# ESP32C3.net
KiCad netlist of a schematic drawn in Altium Designer
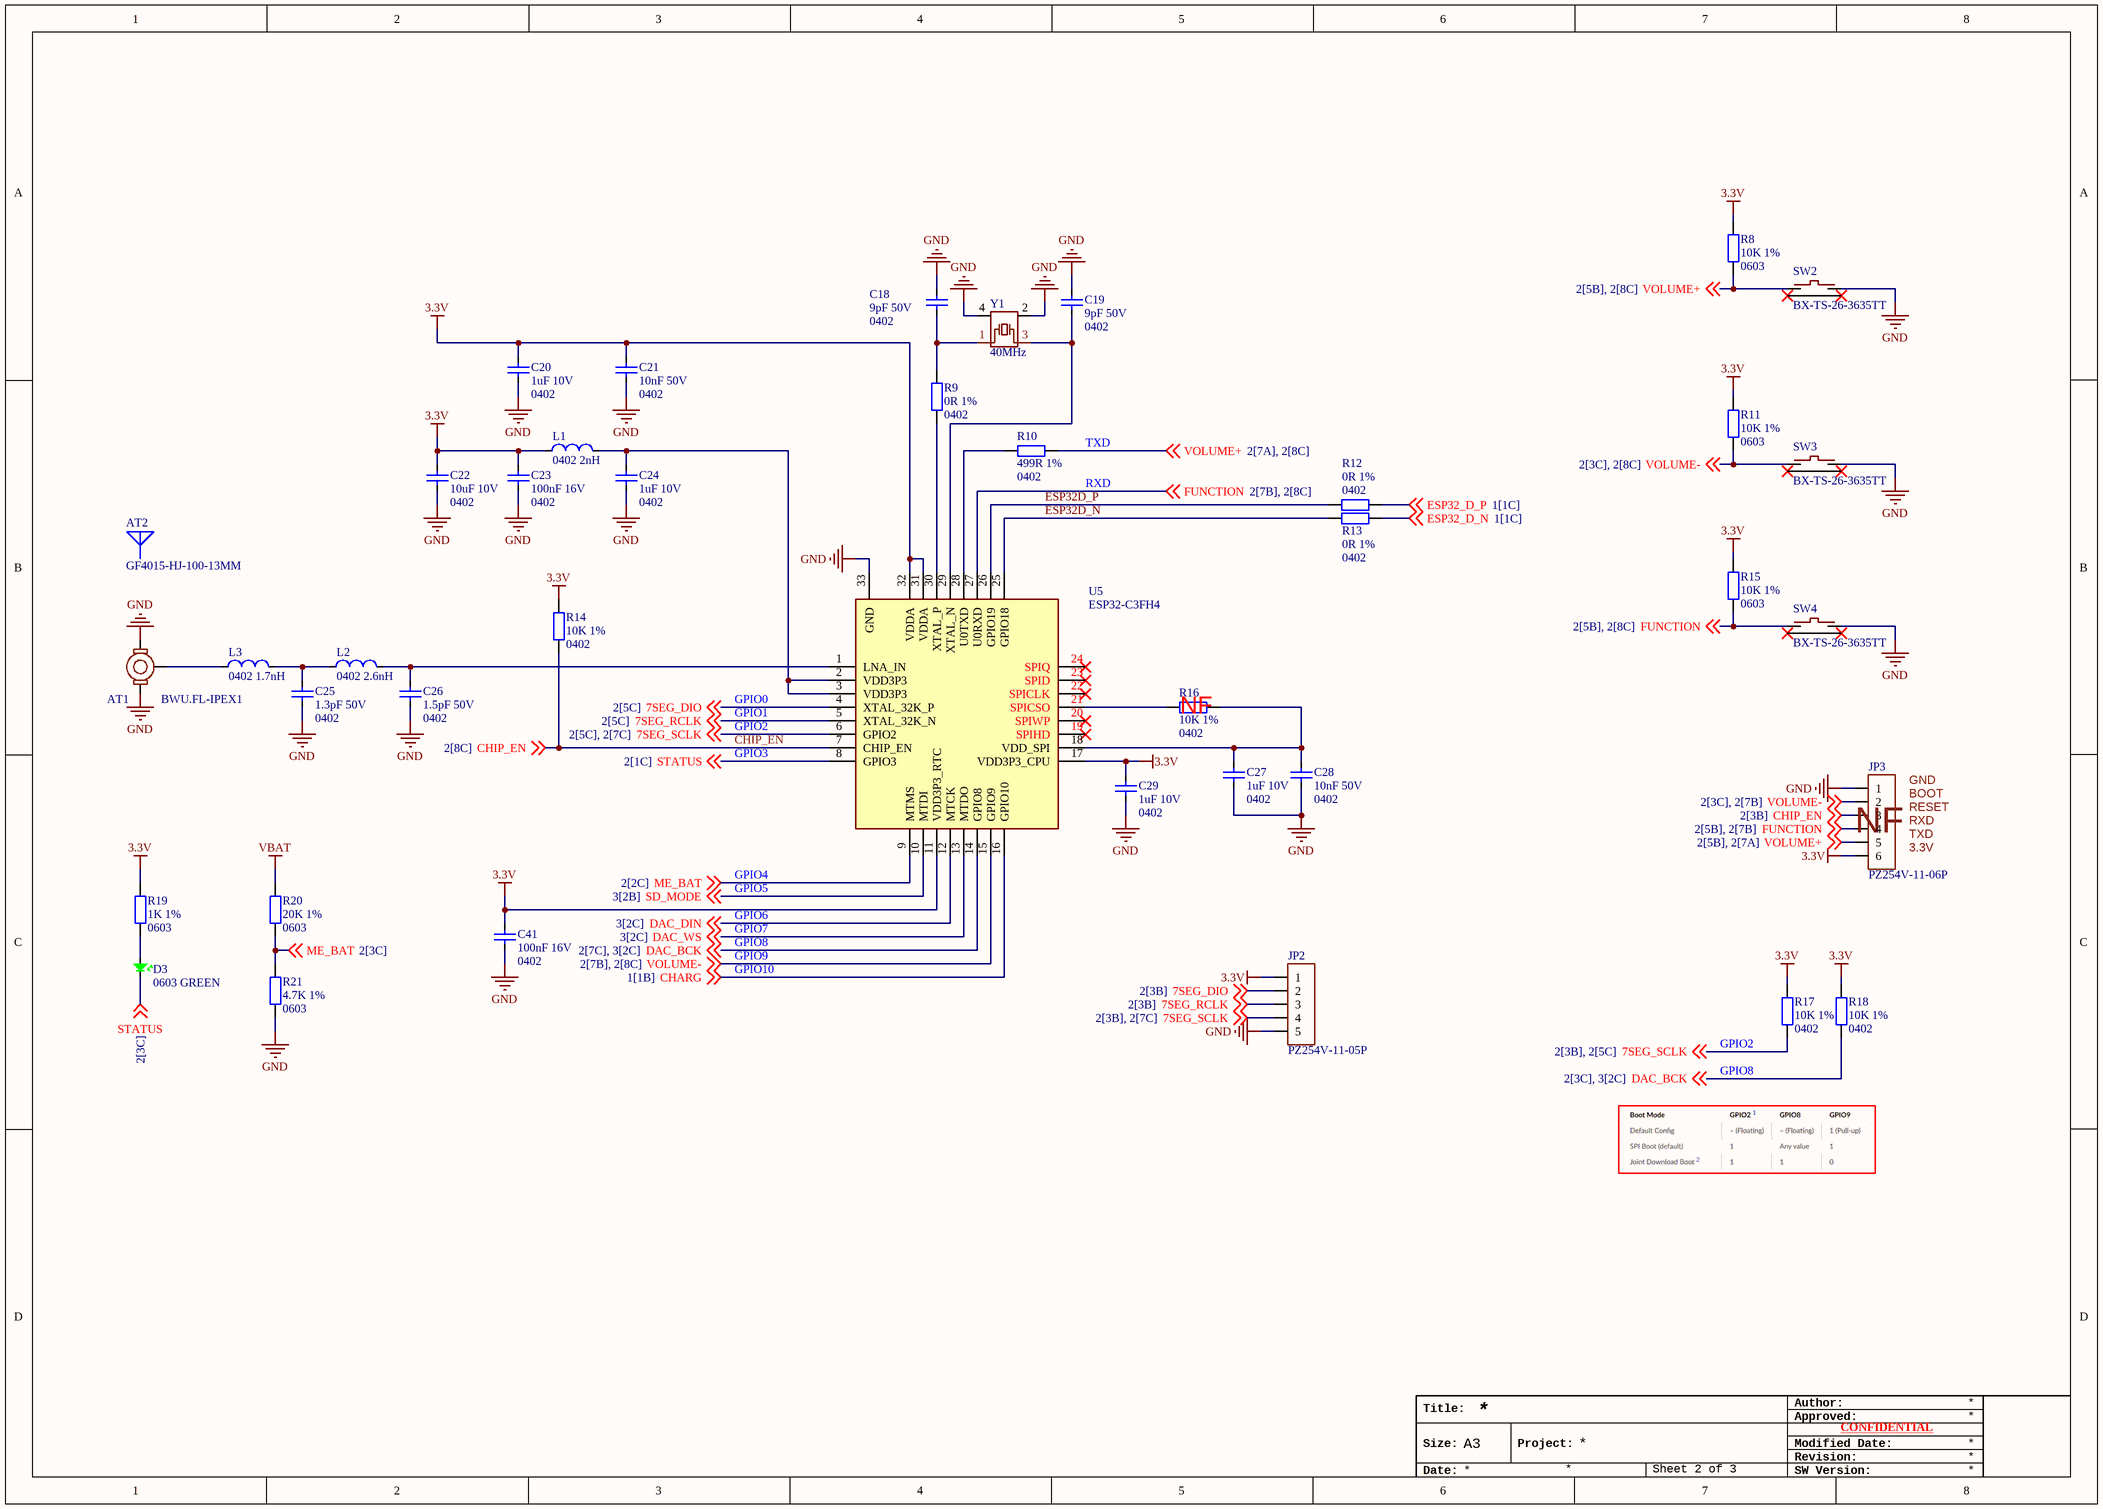
[diagram p0: ESP32C3.SchDoc]

(export (version "E")
  (design (tool "Eeschema 10.0.6"))
  (components
    (comp (ref "AT1")
      (value "BWU.FL-IPEX1")
      (footprint "IPEX-SMD_BWIPX-1-001E")
      (description "1 Inner pin IPEX Board-End 1.25mm 6GHz 50Ω 2mm SMD Coaxial Connectors (RF) ROHS")
      (fields (field (name "MANUFACTURER") "BAT WIRELESS") (field (name "LCSC PART") "C5137195"))
      (libsource (lib "Antenna") (part "BAT WIRELESS BWU.FL-IPEX1"))
    )
    (comp (ref "AT2")
      (value "GF4015-HJ-100-13MM")
      (footprint "GF4015-HJ-100-13MM")
      (description "Ipex 2.4Ghz Antenna")
      (fields (field (name "MANUFACTURER") "Fudong"))
      (libsource (lib "Antenna") (part "GF4015-HJ-100-13MM"))
    )
    (comp (ref "C18")
      (value "9pF 50V")
      (footprint "C0402_2")
      (description "50V 9pF C0G 0402 Multilayer Ceramic Capacitors MLCC - SMD/SMT ROHS")
      (fields
        (field (name "MANUFACTURER") "FH (Guangdong Fenghua Advanced Tech)")
        (field (name "MANUFACTURE PART NUMBER") "0402CG9R0C500NT")
        (field (name "PACKAGE") "0402")
      )
      (libsource (lib "Capacitor") (part "C0402_MLCC_9pF_50V"))
    )
    (comp (ref "C19")
      (value "9pF 50V")
      (footprint "C0402_2")
      (description "50V 9pF C0G 0402 Multilayer Ceramic Capacitors MLCC - SMD/SMT ROHS")
      (fields
        (field (name "MANUFACTURER") "FH (Guangdong Fenghua Advanced Tech)")
        (field (name "MANUFACTURE PART NUMBER") "0402CG9R0C500NT")
        (field (name "PACKAGE") "0402")
      )
      (libsource (lib "Capacitor") (part "C0402_MLCC_9pF_50V"))
    )
    (comp (ref "C20")
      (value "1uF 10V")
      (footprint "C0402_2")
      (description "10V 1uF X5R ±10% 0402 Multilayer Ceramic Capacitors MLCC - SMD/SMT ROHS")
      (fields
        (field (name "MANUFACTURER") "Samsung Electro-Mechanics")
        (field (name "MANUFACTURE PART NUMBER") "CL05A105KP5NNNC")
        (field (name "PACKAGE") "0402")
      )
      (libsource (lib "Capacitor") (part "C0402_MLCC_1uF_10V"))
    )
    (comp (ref "C21")
      (value "10nF 50V")
      (footprint "C0402_2")
      (description "50V 10nF X7R ±5% 0402 Multilayer Ceramic Capacitors MLCC - SMD/SMT ROHS")
      (fields
        (field (name "MANUFACTURER") "FH (Guangdong Fenghua Advanced Tech)")
        (field (name "MANUFACTURE PART NUMBER") "0402B103J500NT")
        (field (name "PACKAGE") "0402")
      )
      (libsource (lib "Capacitor") (part "C0402_MLCC_10nF_50V"))
    )
    (comp (ref "C22")
      (value "10uF 10V")
      (footprint "C0402_2")
      (description "10V 10uF X5R ±20% 0402 Multilayer Ceramic Capacitors MLCC - SMD/SMT ROHS")
      (fields
        (field (name "MANUFACTURER") "Samsung Electro-Mechanics")
        (field (name "MANUFACTURE PART NUMBER") "CL05A106MP5NUNC")
        (field (name "PACKAGE") "0402")
      )
      (libsource (lib "Capacitor") (part "C0402_MLCC_10uF_10V"))
    )
    (comp (ref "C23")
      (value "100nF 16V")
      (footprint "C0402_2")
      (description "16V 100nF X7R ±10% 0402 Multilayer Ceramic Capacitors MLCC - SMD/SMT ROHS")
      (fields
        (field (name "MANUFACTURER") "YAGEO")
        (field (name "MANUFACTURE PART NUMBER") "CC0402KRX7R7BB104")
        (field (name "PACKAGE") "0402")
      )
      (libsource (lib "Capacitor") (part "C0402_MLCC_100nF_16V"))
    )
    (comp (ref "C24")
      (value "1uF 10V")
      (footprint "C0402_2")
      (description "10V 1uF X5R ±10% 0402 Multilayer Ceramic Capacitors MLCC - SMD/SMT ROHS")
      (fields
        (field (name "MANUFACTURER") "Samsung Electro-Mechanics")
        (field (name "MANUFACTURE PART NUMBER") "CL05A105KP5NNNC")
        (field (name "PACKAGE") "0402")
      )
      (libsource (lib "Capacitor") (part "C0402_MLCC_1uF_10V"))
    )
    (comp (ref "C25")
      (value "1.3pF 50V")
      (footprint "C0402_2")
      (description "50V 1.3pF C0G 0402 Multilayer Ceramic Capacitors MLCC - SMD/SMT ROHS")
      (fields
        (field (name "MANUFACTURER") "Murata Electronics")
        (field (name "MANUFACTURE PART NUMBER") "GJM1555C1H1R3WB01D")
        (field (name "PACKAGE") "0402")
      )
      (libsource (lib "Capacitor") (part "C0402_MLCC_1.3pF_50V"))
    )
    (comp (ref "C26")
      (value "1.5pF 50V")
      (footprint "C0402_2")
      (description "50V 1.5pF NP0 0402 Multilayer Ceramic Capacitors MLCC - SMD/SMT ROHS")
      (fields
        (field (name "MANUFACTURER") "Walsin Tech Corp")
        (field (name "MANUFACTURE PART NUMBER") "RF15N1R5B500CT")
        (field (name "PACKAGE") "0402")
      )
      (libsource (lib "Capacitor") (part "C0402_MLCC_1.5pF_50V"))
    )
    (comp (ref "C27")
      (value "1uF 10V")
      (footprint "C0402_2")
      (description "10V 1uF X5R ±10% 0402 Multilayer Ceramic Capacitors MLCC - SMD/SMT ROHS")
      (fields
        (field (name "MANUFACTURER") "Samsung Electro-Mechanics")
        (field (name "MANUFACTURE PART NUMBER") "CL05A105KP5NNNC")
        (field (name "PACKAGE") "0402")
      )
      (libsource (lib "Capacitor") (part "C0402_MLCC_1uF_10V"))
    )
    (comp (ref "C28")
      (value "10nF 50V")
      (footprint "C0402_2")
      (description "50V 10nF X7R ±5% 0402 Multilayer Ceramic Capacitors MLCC - SMD/SMT ROHS")
      (fields
        (field (name "MANUFACTURER") "FH (Guangdong Fenghua Advanced Tech)")
        (field (name "MANUFACTURE PART NUMBER") "0402B103J500NT")
        (field (name "PACKAGE") "0402")
      )
      (libsource (lib "Capacitor") (part "C0402_MLCC_10nF_50V"))
    )
    (comp (ref "C29")
      (value "1uF 10V")
      (footprint "C0402_2")
      (description "10V 1uF X5R ±10% 0402 Multilayer Ceramic Capacitors MLCC - SMD/SMT ROHS")
      (fields
        (field (name "MANUFACTURER") "Samsung Electro-Mechanics")
        (field (name "MANUFACTURE PART NUMBER") "CL05A105KP5NNNC")
        (field (name "PACKAGE") "0402")
      )
      (libsource (lib "Capacitor") (part "C0402_MLCC_1uF_10V"))
    )
    (comp (ref "C41")
      (value "100nF 16V")
      (footprint "C0402_2")
      (description "16V 100nF X7R ±10% 0402 Multilayer Ceramic Capacitors MLCC - SMD/SMT ROHS")
      (fields
        (field (name "MANUFACTURER") "YAGEO")
        (field (name "MANUFACTURE PART NUMBER") "CC0402KRX7R7BB104")
        (field (name "PACKAGE") "0402")
      )
      (libsource (lib "Capacitor") (part "C0402_MLCC_100nF_16V"))
    )
    (comp (ref "D3")
      (value "0603 GREEN")
      (footprint "LED0603_GREEN")
      (fields
        (field (name "MANUFACTURER") "Amicc")
        (field (name "MANUFACTURE PART NUMBER") "A-SP192DGHC-C01-4T")
        (field (name "LCSC PART") "C19171301")
      )
      (libsource (lib "LED") (part "L0603_GREEN"))
    )
    (comp (ref "JP2")
      (value "PZ254V-11-05P")
      (footprint "JP5_M_SMD - 2")
      (fields (field (name "MANUFACTURER") "XFCN") (field (name "LCSC PART") "C492404"))
      (libsource (lib "Connector") (part "XFCN PZ254V-11-05P"))
    )
    (comp (ref "JP3")
      (value "PZ254V-11-06P")
      (footprint "JP6_M_2")
      (fields (field (name "MANUFACTURER") "XFCN") (field (name "LCSC PART") "C492405"))
      (libsource (lib "Connector") (part "PZ254V-11-06P"))
    )
    (comp (ref "L1")
      (value "0402 2nH")
      (footprint "L0402")
      (description "900mA 2nH 90mΩ 0402 Inductors (SMD) ROHS")
      (fields
        (field (name "MANUFACTURER") "Murata Electronics")
        (field (name "MANUFACTURE PART NUMBER") "LQG15HS2N0S02D")
      )
      (libsource (lib "Inductor") (part "L0402_2nH_900mA"))
    )
    (comp (ref "L2")
      (value "0402 2.6nH")
      (footprint "L0402")
      (description "1.95A 2.6nH 0402 Power Inductors ROHS")
      (fields
        (field (name "MANUFACTURER") "Murata Electronics")
        (field (name "MANUFACTURE PART NUMBER") "LQW15AN2N6G80D")
      )
      (libsource (lib "Inductor") (part "L0402_2.6nH_1.95A"))
    )
    (comp (ref "L3")
      (value "0402 1.7nH")
      (footprint "L0402")
      (description "1.15A 1.7nH 0402 Power Inductors ROHS")
      (fields
        (field (name "MANUFACTURER") "Murata Electronics")
        (field (name "MANUFACTURE PART NUMBER") "LQW15AN1N7C80D")
      )
      (libsource (lib "Inductor") (part "L0402_1.7nH_1.15A"))
    )
    (comp (ref "R8")
      (value "10K 1%")
      (footprint "RES_SMD_0603")
      (description "10 kOhms ±1% 0.1W, 1/10W Chip Resistor 0603 (1608 Metric) Moisture Resistant Thick Film")
      (fields
        (field (name "MANUFACTURER") "YAGEO")
        (field (name "MANUFACTURE PART NUMBER") "RC0603FR-0710KL")
        (field (name "PACKAGE") "0603")
      )
      (libsource (lib "Resistor") (part "R0603_10K"))
    )
    (comp (ref "R9")
      (value "0R 1%")
      (footprint "RES_SMD_0402")
      (description "0 Ohms Jumper Chip Resistor 0402 (1005 Metric) Moisture Resistant Thick Film")
      (fields
        (field (name "MANUFACTURER") "YAGEO")
        (field (name "MANUFACTURE PART NUMBER") "RC0402JR-070RL")
        (field (name "PACKAGE") "0402")
      )
      (libsource (lib "Resistor") (part "R0402_0R"))
    )
    (comp (ref "R10")
      (value "499R 1%")
      (footprint "RES_SMD_0402")
      (description "499 Ohms ±1% 0.063W, 1/16W Chip Resistor 0402 (1005 Metric) Moisture Resistant Thick Film")
      (fields
        (field (name "MANUFACTURER") "YAGEO")
        (field (name "MANUFACTURE PART NUMBER") "RC0402FR-13499RL")
        (field (name "PACKAGE") "0402")
      )
      (libsource (lib "Resistor") (part "R0402_499R"))
    )
    (comp (ref "R11")
      (value "10K 1%")
      (footprint "RES_SMD_0603")
      (description "10 kOhms ±1% 0.1W, 1/10W Chip Resistor 0603 (1608 Metric) Moisture Resistant Thick Film")
      (fields
        (field (name "MANUFACTURER") "YAGEO")
        (field (name "MANUFACTURE PART NUMBER") "RC0603FR-0710KL")
        (field (name "PACKAGE") "0603")
      )
      (libsource (lib "Resistor") (part "R0603_10K"))
    )
    (comp (ref "R12")
      (value "0R 1%")
      (footprint "RES_SMD_0402")
      (description "0 Ohms Jumper Chip Resistor 0402 (1005 Metric) Moisture Resistant Thick Film")
      (fields
        (field (name "MANUFACTURER") "YAGEO")
        (field (name "MANUFACTURE PART NUMBER") "RC0402JR-070RL")
        (field (name "PACKAGE") "0402")
      )
      (libsource (lib "Resistor") (part "R0402_0R"))
    )
    (comp (ref "R13")
      (value "0R 1%")
      (footprint "RES_SMD_0402")
      (description "0 Ohms Jumper Chip Resistor 0402 (1005 Metric) Moisture Resistant Thick Film")
      (fields
        (field (name "MANUFACTURER") "YAGEO")
        (field (name "MANUFACTURE PART NUMBER") "RC0402JR-070RL")
        (field (name "PACKAGE") "0402")
      )
      (libsource (lib "Resistor") (part "R0402_0R"))
    )
    (comp (ref "R14")
      (value "10K 1%")
      (footprint "RES_SMD_0402")
      (description "10 kOhms ±1% 0.063W, 1/16W Chip Resistor 0402 (1005 Metric) Moisture Resistant Thick Film")
      (fields
        (field (name "MANUFACTURER") "YAGEO")
        (field (name "MANUFACTURE PART NUMBER") "RC0402FR-0710KL")
        (field (name "PACKAGE") "0402")
      )
      (libsource (lib "Resistor") (part "R0402_10K"))
    )
    (comp (ref "R15")
      (value "10K 1%")
      (footprint "RES_SMD_0603")
      (description "10 kOhms ±1% 0.1W, 1/10W Chip Resistor 0603 (1608 Metric) Moisture Resistant Thick Film")
      (fields
        (field (name "MANUFACTURER") "YAGEO")
        (field (name "MANUFACTURE PART NUMBER") "RC0603FR-0710KL")
        (field (name "PACKAGE") "0603")
      )
      (libsource (lib "Resistor") (part "R0603_10K"))
    )
    (comp (ref "R16")
      (value "10K 1%")
      (footprint "RES_SMD_0402")
      (description "10 kOhms ±1% 0.063W, 1/16W Chip Resistor 0402 (1005 Metric) Moisture Resistant Thick Film")
      (fields
        (field (name "MANUFACTURER") "YAGEO")
        (field (name "MANUFACTURE PART NUMBER") "RC0402FR-0710KL")
        (field (name "PACKAGE") "0402")
      )
      (libsource (lib "Resistor") (part "R0402_10K"))
    )
    (comp (ref "R17")
      (value "10K 1%")
      (footprint "RES_SMD_0402")
      (description "10 kOhms ±1% 0.063W, 1/16W Chip Resistor 0402 (1005 Metric) Moisture Resistant Thick Film")
      (fields
        (field (name "MANUFACTURER") "YAGEO")
        (field (name "MANUFACTURE PART NUMBER") "RC0402FR-0710KL")
        (field (name "PACKAGE") "0402")
      )
      (libsource (lib "Resistor") (part "R0402_10K"))
    )
    (comp (ref "R18")
      (value "10K 1%")
      (footprint "RES_SMD_0402")
      (description "10 kOhms ±1% 0.063W, 1/16W Chip Resistor 0402 (1005 Metric) Moisture Resistant Thick Film")
      (fields
        (field (name "MANUFACTURER") "YAGEO")
        (field (name "MANUFACTURE PART NUMBER") "RC0402FR-0710KL")
        (field (name "PACKAGE") "0402")
      )
      (libsource (lib "Resistor") (part "R0402_10K"))
    )
    (comp (ref "R19")
      (value "1K 1%")
      (footprint "RES_SMD_0603")
      (description "1 kOhms ±1% 0.1W, 1/10W Chip Resistor 0603 (1608 Metric) Moisture Resistant Thick Film")
      (fields
        (field (name "MANUFACTURER") "YAGEO")
        (field (name "MANUFACTURE PART NUMBER") "RC0603FR-071KL")
        (field (name "PACKAGE") "0603")
      )
      (libsource (lib "Resistor") (part "R0603_1K"))
    )
    (comp (ref "R20")
      (value "20K 1%")
      (footprint "RES_SMD_0603")
      (description "100mW Thick Film Resistors 75V ±100ppm/℃ ±1% 20kΩ 0603 Chip Resistor - Surface Mount ROHS")
      (fields
        (field (name "MANUFACTURER") "YAGEO")
        (field (name "MANUFACTURE PART NUMBER") "RC0603FR-0720KL")
        (field (name "PACKAGE") "0603")
      )
      (libsource (lib "Resistor") (part "R0603_20K"))
    )
    (comp (ref "R21")
      (value "4.7K 1%")
      (footprint "RES_SMD_0603")
      (description "4.7 kOhms ±1% 0.1W, 1/10W Chip Resistor 0603 (1608 Metric) Moisture Resistant Thick Film")
      (fields
        (field (name "MANUFACTURER") "YAGEO")
        (field (name "MANUFACTURE PART NUMBER") "RC0603FR-074K7L")
        (field (name "PACKAGE") "0603")
      )
      (libsource (lib "Resistor") (part "R0603_4.7K"))
    )
    (comp (ref "SW2")
      (value "BX-TS-26-3635TT")
      (footprint "BX-TS-26-3635TT")
      (fields (field (name "MANUFACTURER") "Bossie") (field (name "MANUFACTURE PART NUMBER") "C18078107"))
      (libsource (lib "Switch") (part "BX-TS-26-3635TT"))
    )
    (comp (ref "SW3")
      (value "BX-TS-26-3635TT")
      (footprint "BX-TS-26-3635TT")
      (fields (field (name "MANUFACTURER") "Bossie") (field (name "MANUFACTURE PART NUMBER") "C18078107"))
      (libsource (lib "Switch") (part "BX-TS-26-3635TT"))
    )
    (comp (ref "SW4")
      (value "BX-TS-26-3635TT")
      (footprint "BX-TS-26-3635TT")
      (fields (field (name "MANUFACTURER") "Bossie") (field (name "MANUFACTURE PART NUMBER") "C18078107"))
      (libsource (lib "Switch") (part "BX-TS-26-3635TT"))
    )
    (comp (ref "U5")
      (value "ESP32-C3FH4")
      (footprint "QFN-32_L5.0-W5.0")
      (description "QFN-32-EP(5x5) Microcontrollers (MCU/MPU/SOC) ROHS")
      (fields (field (name "MANUFACTURER") "Espressif Systems") (field (name "LCSC PART") "C2858491"))
      (libsource (lib "MCU") (part "ESP32-C3FH4"))
    )
    (comp (ref "Y1")
      (value "40MHz")
      (footprint "SMD3225-4P")
      (description "40MHz Surface Mount Crystal 9pF ±10ppm ±10ppm SMD3225-4P Crystals ROHS")
      (fields
        (field (name "MANUFACTURER") "TOGNJING")
        (field (name "MANUFACTURE PART NUMBER") "XTM32040000FT00351001")
      )
      (libsource (lib "Crystal") (part "40Mhz-3225-4P"))
    )
  )
  (nets
    (net (code "1") (name "/ESP32D_N") (class "Default")
      (node (ref "R13") (pin "2") (pinfunction "2_2") (pintype "passive"))
      (node (ref "U5") (pin "25") (pinfunction "GPIO18_25") (pintype "passive"))
    )
    (net (code "2") (name "/ESP32D_P") (class "Default")
      (node (ref "R12") (pin "2") (pinfunction "2_2") (pintype "passive"))
      (node (ref "U5") (pin "26") (pinfunction "GPIO19_26") (pintype "passive"))
    )
    (net (code "3") (name "3.3V") (class "Default")
      (node (ref "C20") (pin "2") (pinfunction "2_2") (pintype "passive"))
      (node (ref "C21") (pin "2") (pinfunction "2_2") (pintype "passive"))
      (node (ref "C22") (pin "2") (pinfunction "2_2") (pintype "passive"))
      (node (ref "C23") (pin "2") (pinfunction "2_2") (pintype "passive"))
      (node (ref "C29") (pin "2") (pinfunction "2_2") (pintype "passive"))
      (node (ref "C41") (pin "2") (pinfunction "2_2") (pintype "passive"))
      (node (ref "JP2") (pin "1") (pinfunction "1_1") (pintype "passive"))
      (node (ref "JP3") (pin "6") (pinfunction "6_6") (pintype "passive"))
      (node (ref "L1") (pin "1") (pinfunction "1_1") (pintype "passive"))
      (node (ref "R11") (pin "2") (pinfunction "2_2") (pintype "passive"))
      (node (ref "R14") (pin "2") (pinfunction "2_2") (pintype "passive"))
      (node (ref "R15") (pin "2") (pinfunction "2_2") (pintype "passive"))
      (node (ref "R17") (pin "2") (pinfunction "2_2") (pintype "passive"))
      (node (ref "R18") (pin "2") (pinfunction "2_2") (pintype "passive"))
      (node (ref "R19") (pin "2") (pinfunction "2_2") (pintype "passive"))
      (node (ref "R8") (pin "2") (pinfunction "2_2") (pintype "passive"))
      (node (ref "U5") (pin "11") (pinfunction "VDD3P3_RTC_11") (pintype "passive"))
      (node (ref "U5") (pin "17") (pinfunction "VDD3P3_CPU_17") (pintype "passive"))
      (node (ref "U5") (pin "31") (pinfunction "VDDA_31") (pintype "passive"))
      (node (ref "U5") (pin "32") (pinfunction "VDDA_32") (pintype "passive"))
    )
    (net (code "4") (name "7SEG_DIO") (class "Default")
      (node (ref "JP2") (pin "2") (pinfunction "2_2") (pintype "passive"))
      (node (ref "U5") (pin "4") (pinfunction "XTAL_32K_P_4") (pintype "passive"))
    )
    (net (code "5") (name "7SEG_RCLK") (class "Default")
      (node (ref "JP2") (pin "3") (pinfunction "3_3") (pintype "passive"))
      (node (ref "U5") (pin "5") (pinfunction "XTAL_32K_N_5") (pintype "passive"))
    )
    (net (code "6") (name "7SEG_SCLK") (class "Default")
      (node (ref "JP2") (pin "4") (pinfunction "4_4") (pintype "passive"))
      (node (ref "R17") (pin "1") (pinfunction "1_1") (pintype "passive"))
      (node (ref "U5") (pin "6") (pinfunction "GPIO2_6") (pintype "passive"))
    )
    (net (code "7") (name "CHARG") (class "Default")
      (node (ref "U5") (pin "16") (pinfunction "GPIO10_16") (pintype "passive"))
    )
    (net (code "8") (name "CHIP_EN") (class "Default")
      (node (ref "JP3") (pin "3") (pinfunction "3_3") (pintype "passive"))
      (node (ref "R14") (pin "1") (pinfunction "1_1") (pintype "passive"))
      (node (ref "U5") (pin "7") (pinfunction "CHIP_EN_7") (pintype "passive"))
    )
    (net (code "9") (name "DAC_BCK") (class "Default")
      (node (ref "R18") (pin "1") (pinfunction "1_1") (pintype "passive"))
      (node (ref "U5") (pin "14") (pinfunction "GPIO8_14") (pintype "passive"))
    )
    (net (code "10") (name "DAC_DIN") (class "Default")
      (node (ref "U5") (pin "12") (pinfunction "MTCK_12") (pintype "passive"))
    )
    (net (code "11") (name "DAC_WS") (class "Default")
      (node (ref "U5") (pin "13") (pinfunction "MTDO_13") (pintype "passive"))
    )
    (net (code "12") (name "ESP32_D_N") (class "Default")
      (node (ref "R13") (pin "1") (pinfunction "1_1") (pintype "passive"))
    )
    (net (code "13") (name "ESP32_D_P") (class "Default")
      (node (ref "R12") (pin "1") (pinfunction "1_1") (pintype "passive"))
    )
    (net (code "14") (name "FUNCTION") (class "Default")
      (node (ref "JP3") (pin "4") (pinfunction "4_4") (pintype "passive"))
      (node (ref "R15") (pin "1") (pinfunction "1_1") (pintype "passive"))
      (node (ref "SW4") (pin "1") (pinfunction "1_1") (pintype "passive"))
      (node (ref "U5") (pin "27") (pinfunction "U0RXD_27") (pintype "passive"))
    )
    (net (code "15") (name "GND") (class "Default")
      (node (ref "AT1") (pin "2") (pinfunction "2_2") (pintype "passive"))
      (node (ref "C18") (pin "2") (pinfunction "2_2") (pintype "passive"))
      (node (ref "C19") (pin "2") (pinfunction "2_2") (pintype "passive"))
      (node (ref "C20") (pin "1") (pinfunction "1_1") (pintype "passive"))
      (node (ref "C21") (pin "1") (pinfunction "1_1") (pintype "passive"))
      (node (ref "C22") (pin "1") (pinfunction "1_1") (pintype "passive"))
      (node (ref "C23") (pin "1") (pinfunction "1_1") (pintype "passive"))
      (node (ref "C24") (pin "1") (pinfunction "1_1") (pintype "passive"))
      (node (ref "C25") (pin "1") (pinfunction "1_1") (pintype "passive"))
      (node (ref "C26") (pin "1") (pinfunction "1_1") (pintype "passive"))
      (node (ref "C27") (pin "1") (pinfunction "1_1") (pintype "passive"))
      (node (ref "C28") (pin "1") (pinfunction "1_1") (pintype "passive"))
      (node (ref "C29") (pin "1") (pinfunction "1_1") (pintype "passive"))
      (node (ref "C41") (pin "1") (pinfunction "1_1") (pintype "passive"))
      (node (ref "JP2") (pin "5") (pinfunction "5_5") (pintype "passive"))
      (node (ref "JP3") (pin "1") (pinfunction "1_1") (pintype "passive"))
      (node (ref "R21") (pin "1") (pinfunction "1_1") (pintype "passive"))
      (node (ref "SW2") (pin "2") (pinfunction "2_2") (pintype "passive"))
      (node (ref "SW3") (pin "2") (pinfunction "2_2") (pintype "passive"))
      (node (ref "SW4") (pin "2") (pinfunction "2_2") (pintype "passive"))
      (node (ref "U5") (pin "33") (pinfunction "GND_33") (pintype "passive"))
      (node (ref "Y1") (pin "2") (pinfunction "2_2") (pintype "passive"))
      (node (ref "Y1") (pin "4") (pinfunction "4_4") (pintype "passive"))
    )
    (net (code "16") (name "ME_BAT") (class "Default")
      (node (ref "R20") (pin "1") (pinfunction "1_1") (pintype "passive"))
      (node (ref "R21") (pin "2") (pinfunction "2_2") (pintype "passive"))
      (node (ref "U5") (pin "9") (pinfunction "MTMS_9") (pintype "passive"))
    )
    (net (code "17") (name "Net-(AT1-Pad1)") (class "Default")
      (node (ref "AT1") (pin "1") (pinfunction "1_1") (pintype "passive"))
      (node (ref "L3") (pin "1") (pinfunction "1_1") (pintype "passive"))
    )
    (net (code "18") (name "Net-(C18-Pad1)") (class "Default")
      (node (ref "C18") (pin "1") (pinfunction "1_1") (pintype "passive"))
      (node (ref "R9") (pin "2") (pinfunction "2_2") (pintype "passive"))
      (node (ref "Y1") (pin "1") (pinfunction "1_1") (pintype "passive"))
    )
    (net (code "19") (name "Net-(C24-Pad2)") (class "Default")
      (node (ref "C24") (pin "2") (pinfunction "2_2") (pintype "passive"))
      (node (ref "L1") (pin "2") (pinfunction "2_2") (pintype "passive"))
      (node (ref "U5") (pin "2") (pinfunction "VDD3P3_2") (pintype "passive"))
      (node (ref "U5") (pin "3") (pinfunction "VDD3P3_3") (pintype "passive"))
    )
    (net (code "20") (name "Net-(C25-Pad2)") (class "Default")
      (node (ref "C25") (pin "2") (pinfunction "2_2") (pintype "passive"))
      (node (ref "L2") (pin "1") (pinfunction "1_1") (pintype "passive"))
      (node (ref "L3") (pin "2") (pinfunction "2_2") (pintype "passive"))
    )
    (net (code "21") (name "Net-(D3-Pad1)") (class "Default")
      (node (ref "D3") (pin "1") (pinfunction "1_1") (pintype "passive"))
      (node (ref "R19") (pin "1") (pinfunction "1_1") (pintype "passive"))
    )
    (net (code "22") (name "Net-(U5-LNA_IN)") (class "Default")
      (node (ref "C26") (pin "2") (pinfunction "2_2") (pintype "passive"))
      (node (ref "L2") (pin "2") (pinfunction "2_2") (pintype "passive"))
      (node (ref "U5") (pin "1") (pinfunction "LNA_IN_1") (pintype "passive"))
    )
    (net (code "23") (name "Net-(U5-SPICSO)") (class "Default")
      (node (ref "R16") (pin "1") (pinfunction "1_1") (pintype "passive"))
      (node (ref "U5") (pin "21") (pinfunction "SPICSO_21") (pintype "passive"))
    )
    (net (code "24") (name "Net-(U5-U0TXD)") (class "Default")
      (node (ref "R10") (pin "1") (pinfunction "1_1") (pintype "passive"))
      (node (ref "U5") (pin "28") (pinfunction "U0TXD_28") (pintype "passive"))
    )
    (net (code "25") (name "Net-(U5-VDD_SPI)") (class "Default")
      (node (ref "C27") (pin "2") (pinfunction "2_2") (pintype "passive"))
      (node (ref "C28") (pin "2") (pinfunction "2_2") (pintype "passive"))
      (node (ref "R16") (pin "2") (pinfunction "2_2") (pintype "passive"))
      (node (ref "U5") (pin "18") (pinfunction "VDD_SPI_18") (pintype "passive"))
    )
    (net (code "26") (name "Net-(U5-XTAL_N)") (class "Default")
      (node (ref "C19") (pin "1") (pinfunction "1_1") (pintype "passive"))
      (node (ref "U5") (pin "29") (pinfunction "XTAL_N_29") (pintype "passive"))
      (node (ref "Y1") (pin "3") (pinfunction "3_3") (pintype "passive"))
    )
    (net (code "27") (name "Net-(U5-XTAL_P)") (class "Default")
      (node (ref "R9") (pin "1") (pinfunction "1_1") (pintype "passive"))
      (node (ref "U5") (pin "30") (pinfunction "XTAL_P_30") (pintype "passive"))
    )
    (net (code "28") (name "SD_MODE") (class "Default")
      (node (ref "U5") (pin "10") (pinfunction "MTDI_10") (pintype "passive"))
    )
    (net (code "29") (name "STATUS") (class "Default")
      (node (ref "D3") (pin "2") (pinfunction "2_2") (pintype "passive"))
      (node (ref "U5") (pin "8") (pinfunction "GPIO3_8") (pintype "passive"))
    )
    (net (code "30") (name "VBAT") (class "Default")
      (node (ref "R20") (pin "2") (pinfunction "2_2") (pintype "passive"))
    )
    (net (code "31") (name "VOLUME+") (class "Default")
      (node (ref "JP3") (pin "5") (pinfunction "5_5") (pintype "passive"))
      (node (ref "R10") (pin "2") (pinfunction "2_2") (pintype "passive"))
      (node (ref "R8") (pin "1") (pinfunction "1_1") (pintype "passive"))
      (node (ref "SW2") (pin "1") (pinfunction "1_1") (pintype "passive"))
    )
    (net (code "32") (name "VOLUME-") (class "Default")
      (node (ref "JP3") (pin "2") (pinfunction "2_2") (pintype "passive"))
      (node (ref "R11") (pin "1") (pinfunction "1_1") (pintype "passive"))
      (node (ref "SW3") (pin "1") (pinfunction "1_1") (pintype "passive"))
      (node (ref "U5") (pin "15") (pinfunction "GPIO9_15") (pintype "passive"))
    )
    (net (code "33") (name "unconnected-(SW2-Pad3)") (class "Default")
      (node (ref "SW2") (pin "3") (pinfunction "3_3") (pintype "passive+no_connect"))
    )
    (net (code "34") (name "unconnected-(SW2-Pad4)") (class "Default")
      (node (ref "SW2") (pin "4") (pinfunction "4_4") (pintype "passive+no_connect"))
    )
    (net (code "35") (name "unconnected-(SW3-Pad3)") (class "Default")
      (node (ref "SW3") (pin "3") (pinfunction "3_3") (pintype "passive+no_connect"))
    )
    (net (code "36") (name "unconnected-(SW3-Pad4)") (class "Default")
      (node (ref "SW3") (pin "4") (pinfunction "4_4") (pintype "passive+no_connect"))
    )
    (net (code "37") (name "unconnected-(SW4-Pad3)") (class "Default")
      (node (ref "SW4") (pin "3") (pinfunction "3_3") (pintype "passive+no_connect"))
    )
    (net (code "38") (name "unconnected-(SW4-Pad4)") (class "Default")
      (node (ref "SW4") (pin "4") (pinfunction "4_4") (pintype "passive+no_connect"))
    )
    (net (code "39") (name "unconnected-(U5-SPICLK-Pad22)") (class "Default")
      (node (ref "U5") (pin "22") (pinfunction "SPICLK_22") (pintype "passive+no_connect"))
    )
    (net (code "40") (name "unconnected-(U5-SPID-Pad23)") (class "Default")
      (node (ref "U5") (pin "23") (pinfunction "SPID_23") (pintype "passive+no_connect"))
    )
    (net (code "41") (name "unconnected-(U5-SPIHD-Pad19)") (class "Default")
      (node (ref "U5") (pin "19") (pinfunction "SPIHD_19") (pintype "passive+no_connect"))
    )
    (net (code "42") (name "unconnected-(U5-SPIQ-Pad24)") (class "Default")
      (node (ref "U5") (pin "24") (pinfunction "SPIQ_24") (pintype "passive+no_connect"))
    )
    (net (code "43") (name "unconnected-(U5-SPIWP-Pad20)") (class "Default")
      (node (ref "U5") (pin "20") (pinfunction "SPIWP_20") (pintype "passive+no_connect"))
    )
  )
)
